# usb-c-pcb.net
KiCad netlist of a schematic drawn in EAGLE
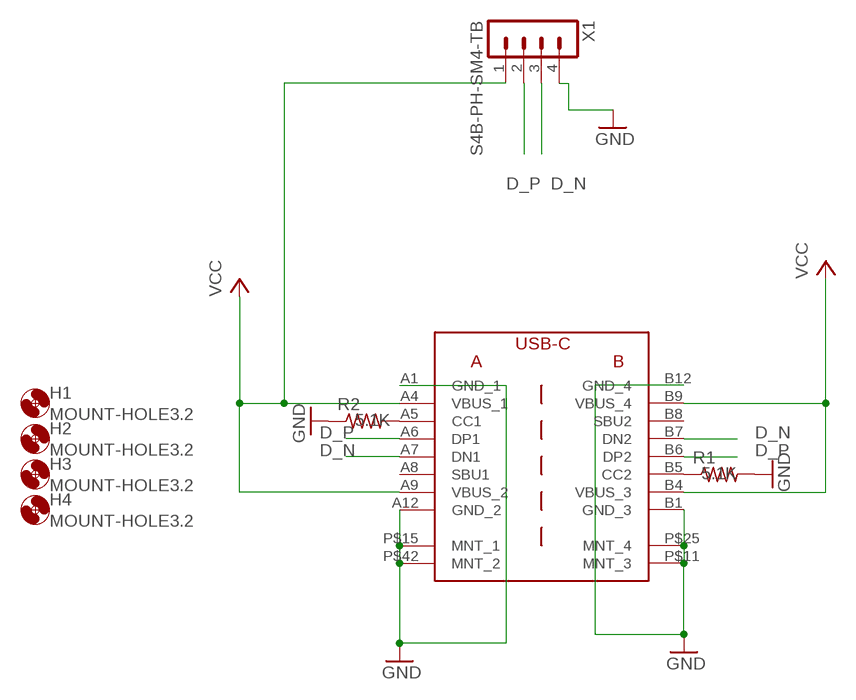
[diagram p0: schematic, sheet 1]

(export (version "E")
  (design (tool "Eeschema 10.0.6"))
  (components
    (comp (ref "H1")
      (value "MOUNT-HOLE3.2")
      (footprint "eagle-import:3,2")
      (libsource (lib "eagle-import") (part "MOUNT-HOLE3.2"))
    )
    (comp (ref "H2")
      (value "MOUNT-HOLE3.2")
      (footprint "eagle-import:3,2")
      (libsource (lib "eagle-import") (part "MOUNT-HOLE3.2"))
    )
    (comp (ref "H3")
      (value "MOUNT-HOLE3.2")
      (footprint "eagle-import:3,2")
      (libsource (lib "eagle-import") (part "MOUNT-HOLE3.2"))
    )
    (comp (ref "H4")
      (value "MOUNT-HOLE3.2")
      (footprint "eagle-import:3,2")
      (libsource (lib "eagle-import") (part "MOUNT-HOLE3.2"))
    )
    (comp (ref "R1")
      (value "5.1K")
      (footprint "eagle-import:R0402")
      (libsource (lib "eagle-import") (part "R-US_R0402"))
    )
    (comp (ref "R2")
      (value "5.1K")
      (footprint "eagle-import:R0402")
      (libsource (lib "eagle-import") (part "R-US_R0402"))
    )
    (comp (ref "U$1")
      (value "USB_TAYPE_C_16P")
      (footprint "eagle-import:USB_TAYPE_C_16P")
      (libsource (lib "eagle-import") (part "USB_TAYPE_C_16P"))
    )
    (comp (ref "X1")
      (value "S4B-PH-SM4-TB")
      (footprint "eagle-import:S4B-PH-SM4-TB")
      (libsource (lib "eagle-import") (part "S4B-PH-SM4-TB"))
    )
  )
  (nets
    (net (code "1") (name "/D_N") (class "Default")
      (node (ref "U$1") (pin "A7") (pinfunction "DN1_A7") (pintype "bidirectional"))
      (node (ref "U$1") (pin "B7") (pinfunction "DN2_B7") (pintype "bidirectional"))
      (node (ref "X1") (pin "3") (pinfunction "3_3") (pintype "passive"))
    )
    (net (code "2") (name "/D_P") (class "Default")
      (node (ref "U$1") (pin "A6") (pinfunction "DP1_A6") (pintype "bidirectional"))
      (node (ref "U$1") (pin "B6") (pinfunction "DP2_B6") (pintype "bidirectional"))
      (node (ref "X1") (pin "2") (pinfunction "2_2") (pintype "passive"))
    )
    (net (code "3") (name "GND") (class "Default")
      (node (ref "R1") (pin "2") (pinfunction "2_2") (pintype "passive"))
      (node (ref "R2") (pin "1") (pinfunction "1_1") (pintype "passive"))
      (node (ref "U$1") (pin "A1") (pinfunction "GND_1_A1") (pintype "bidirectional"))
      (node (ref "U$1") (pin "A12") (pinfunction "GND_2_A12") (pintype "bidirectional"))
      (node (ref "U$1") (pin "B1") (pinfunction "GND_3_B1") (pintype "bidirectional"))
      (node (ref "U$1") (pin "B12") (pinfunction "GND_4_B12") (pintype "bidirectional"))
      (node (ref "U$1") (pin "P$11") (pinfunction "MNT_3_P$11") (pintype "bidirectional"))
      (node (ref "U$1") (pin "P$15") (pinfunction "MNT_1_P$15") (pintype "bidirectional"))
      (node (ref "U$1") (pin "P$25") (pinfunction "MNT_4_P$25") (pintype "bidirectional"))
      (node (ref "U$1") (pin "P$42") (pinfunction "MNT_2_P$42") (pintype "bidirectional"))
      (node (ref "X1") (pin "4") (pinfunction "4_4") (pintype "passive"))
    )
    (net (code "4") (name "Net-(U$1-CC1)") (class "Default")
      (node (ref "R2") (pin "2") (pinfunction "2_2") (pintype "passive"))
      (node (ref "U$1") (pin "A5") (pinfunction "CC1_A5") (pintype "bidirectional"))
    )
    (net (code "5") (name "Net-(U$1-CC2)") (class "Default")
      (node (ref "R1") (pin "1") (pinfunction "1_1") (pintype "passive"))
      (node (ref "U$1") (pin "B5") (pinfunction "CC2_B5") (pintype "bidirectional"))
    )
    (net (code "6") (name "VCC") (class "Default")
      (node (ref "U$1") (pin "A4") (pinfunction "VBUS_1_A4") (pintype "bidirectional"))
      (node (ref "U$1") (pin "A9") (pinfunction "VBUS_2_A9") (pintype "bidirectional"))
      (node (ref "U$1") (pin "B4") (pinfunction "VBUS_3_B4") (pintype "bidirectional"))
      (node (ref "U$1") (pin "B9") (pinfunction "VBUS_4_B9") (pintype "bidirectional"))
      (node (ref "X1") (pin "1") (pinfunction "1_1") (pintype "passive"))
    )
    (net (code "7") (name "unconnected-(U$1-SBU1-PadA8)") (class "Default")
      (node (ref "U$1") (pin "A8") (pinfunction "SBU1_A8") (pintype "bidirectional"))
    )
    (net (code "8") (name "unconnected-(U$1-SBU2-PadB8)") (class "Default")
      (node (ref "U$1") (pin "B8") (pinfunction "SBU2_B8") (pintype "bidirectional"))
    )
  )
)
